# control_unit_v_1_1.net
KiCad netlist of a schematic drawn in Altium Designer
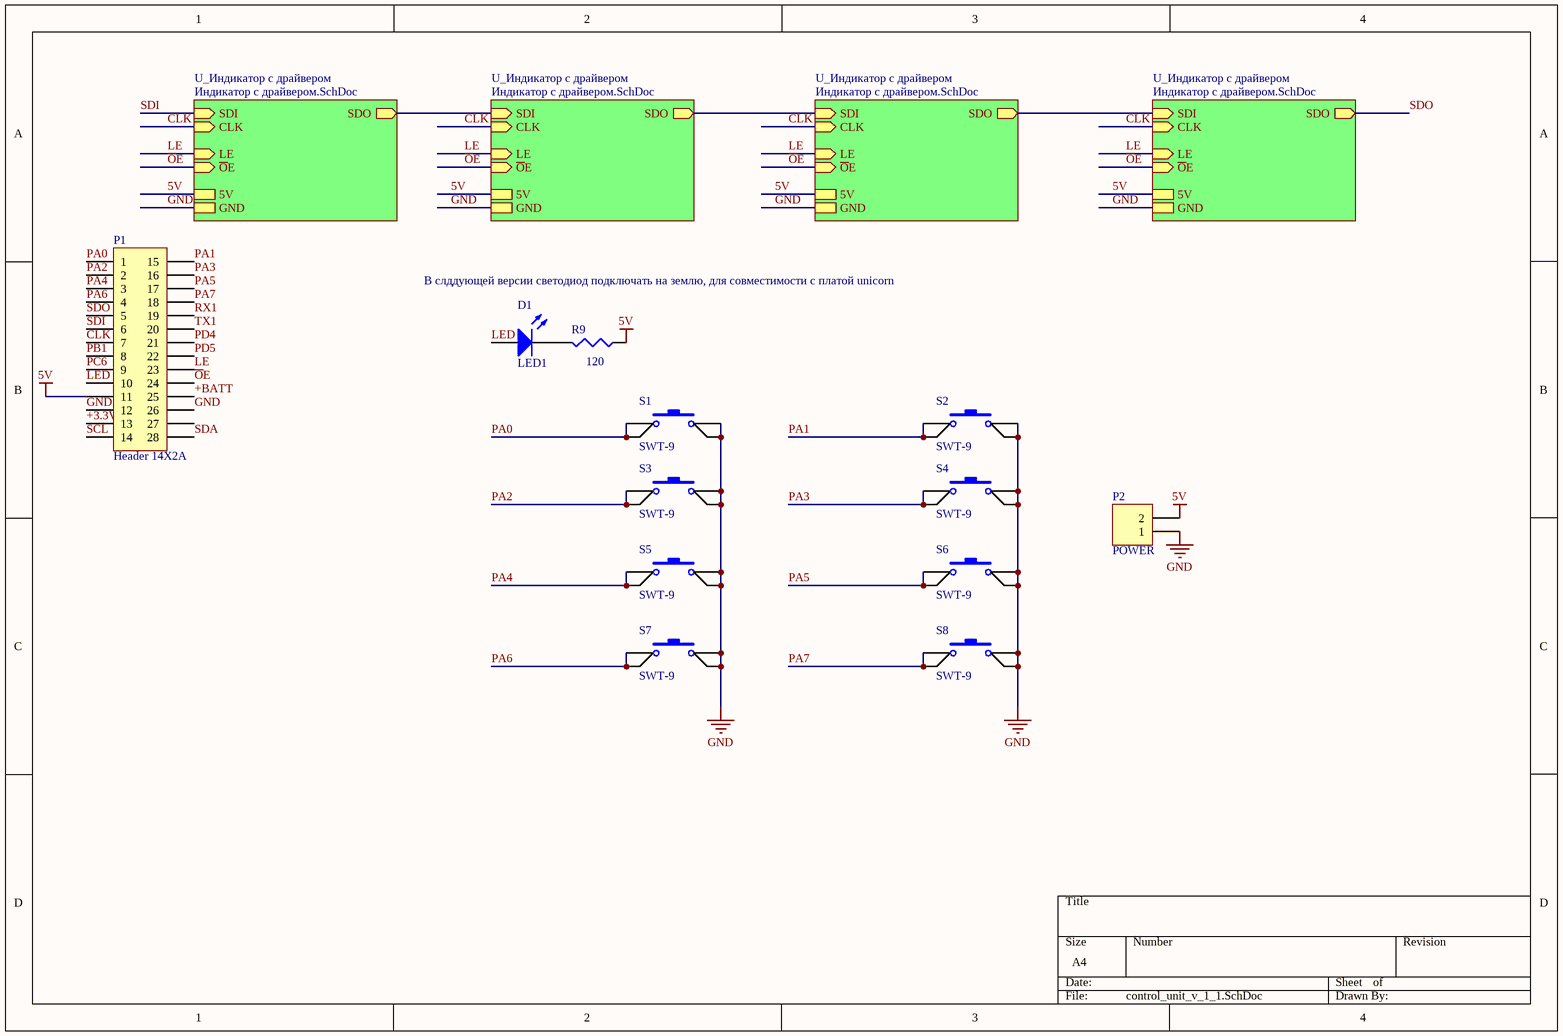
[diagram p0: control_unit_v_1_1.SchDoc]

(export (version "E")
  (design (tool "Eeschema 10.0.6"))
  (components
    (comp (ref "D1")
      (value "LED1")
      (footprint "LED-1")
      (description "Typical RED GaAs LED")
      (fields (field (name "PUBLISHER") "Altium Limited"))
      (libsource (lib "Miscellaneous Devices") (part "LED1"))
    )
    (comp (ref "P1")
      (value "Header 14X2A")
      (footprint "HDR2X14_CEN")
      (description "Header, 14-Pin, Dual row")
      (fields (field (name "PUBLISHER") "Altium Limited"))
      (libsource (lib "Miscellaneous Connectors") (part "Header 14X2A"))
    )
    (comp (ref "P2")
      (value "POWER")
      (footprint "HDR1X2H")
      (description "Header, 2-Pin, Right Angle")
      (fields (field (name "PUBLISHER") "Altium Limited"))
      (libsource (lib "Miscellaneous Connectors") (part "Header 2H"))
    )
    (comp (ref "R9")
      (value "120")
      (footprint "RESC1608L")
      (description "Resistor")
      (fields (field (name "Comment") "Res3") (field (name "PUBLISHER") "Altium Limited"))
      (libsource (lib "Miscellaneous Devices") (part "Res3"))
    )
    (comp (ref "S1")
      (value "SWT-9")
      (footprint "SWT-9")
      (description "Switch")
      (libsource (lib "LibX") (part "SWT-9"))
    )
    (comp (ref "S2")
      (value "SWT-9")
      (footprint "SWT-9")
      (description "Switch")
      (libsource (lib "LibX") (part "SWT-9"))
    )
    (comp (ref "S3")
      (value "SWT-9")
      (footprint "SWT-9")
      (description "Switch")
      (libsource (lib "LibX") (part "SWT-9"))
    )
    (comp (ref "S4")
      (value "SWT-9")
      (footprint "SWT-9")
      (description "Switch")
      (libsource (lib "LibX") (part "SWT-9"))
    )
    (comp (ref "S5")
      (value "SWT-9")
      (footprint "SWT-9")
      (description "Switch")
      (libsource (lib "LibX") (part "SWT-9"))
    )
    (comp (ref "S6")
      (value "SWT-9")
      (footprint "SWT-9")
      (description "Switch")
      (libsource (lib "LibX") (part "SWT-9"))
    )
    (comp (ref "S7")
      (value "SWT-9")
      (footprint "SWT-9")
      (description "Switch")
      (libsource (lib "LibX") (part "SWT-9"))
    )
    (comp (ref "S8")
      (value "SWT-9")
      (footprint "SWT-9")
      (description "Switch")
      (libsource (lib "LibX") (part "SWT-9"))
    )
  )
  (nets
    (net (code "1") (name "/+3.3V") (class "Default")
      (node (ref "P1") (pin "13") (pinfunction "13_13") (pintype "passive"))
    )
    (net (code "2") (name "/+BATT") (class "Default")
      (node (ref "P1") (pin "25") (pinfunction "25_25") (pintype "passive"))
    )
    (net (code "3") (name "/CLK") (class "Default")
      (node (ref "P1") (pin "7") (pinfunction "7_7") (pintype "passive"))
    )
    (net (code "4") (name "/LE") (class "Default")
      (node (ref "P1") (pin "23") (pinfunction "23_23") (pintype "passive"))
    )
    (net (code "5") (name "/LED") (class "Default")
      (node (ref "D1") (pin "1") (pinfunction "A_1") (pintype "passive"))
      (node (ref "P1") (pin "10") (pinfunction "10_10") (pintype "passive"))
    )
    (net (code "6") (name "/PA0") (class "Default")
      (node (ref "P1") (pin "1") (pinfunction "1_1") (pintype "passive"))
      (node (ref "S1") (pin "1") (pinfunction "1_1") (pintype "passive"))
      (node (ref "S1") (pin "2") (pinfunction "2_2") (pintype "passive"))
    )
    (net (code "7") (name "/PA1") (class "Default")
      (node (ref "P1") (pin "15") (pinfunction "15_15") (pintype "passive"))
      (node (ref "S2") (pin "1") (pinfunction "1_1") (pintype "passive"))
      (node (ref "S2") (pin "2") (pinfunction "2_2") (pintype "passive"))
    )
    (net (code "8") (name "/PA2") (class "Default")
      (node (ref "P1") (pin "2") (pinfunction "2_2") (pintype "passive"))
      (node (ref "S3") (pin "1") (pinfunction "1_1") (pintype "passive"))
      (node (ref "S3") (pin "2") (pinfunction "2_2") (pintype "passive"))
    )
    (net (code "9") (name "/PA3") (class "Default")
      (node (ref "P1") (pin "16") (pinfunction "16_16") (pintype "passive"))
      (node (ref "S4") (pin "1") (pinfunction "1_1") (pintype "passive"))
      (node (ref "S4") (pin "2") (pinfunction "2_2") (pintype "passive"))
    )
    (net (code "10") (name "/PA4") (class "Default")
      (node (ref "P1") (pin "3") (pinfunction "3_3") (pintype "passive"))
      (node (ref "S5") (pin "1") (pinfunction "1_1") (pintype "passive"))
      (node (ref "S5") (pin "2") (pinfunction "2_2") (pintype "passive"))
    )
    (net (code "11") (name "/PA5") (class "Default")
      (node (ref "P1") (pin "17") (pinfunction "17_17") (pintype "passive"))
      (node (ref "S6") (pin "1") (pinfunction "1_1") (pintype "passive"))
      (node (ref "S6") (pin "2") (pinfunction "2_2") (pintype "passive"))
    )
    (net (code "12") (name "/PA6") (class "Default")
      (node (ref "P1") (pin "4") (pinfunction "4_4") (pintype "passive"))
      (node (ref "S7") (pin "1") (pinfunction "1_1") (pintype "passive"))
      (node (ref "S7") (pin "2") (pinfunction "2_2") (pintype "passive"))
    )
    (net (code "13") (name "/PA7") (class "Default")
      (node (ref "P1") (pin "18") (pinfunction "18_18") (pintype "passive"))
      (node (ref "S8") (pin "1") (pinfunction "1_1") (pintype "passive"))
      (node (ref "S8") (pin "2") (pinfunction "2_2") (pintype "passive"))
    )
    (net (code "14") (name "/PB1") (class "Default")
      (node (ref "P1") (pin "8") (pinfunction "8_8") (pintype "passive"))
    )
    (net (code "15") (name "/PC6") (class "Default")
      (node (ref "P1") (pin "9") (pinfunction "9_9") (pintype "passive"))
    )
    (net (code "16") (name "/PD4") (class "Default")
      (node (ref "P1") (pin "21") (pinfunction "21_21") (pintype "passive"))
    )
    (net (code "17") (name "/PD5") (class "Default")
      (node (ref "P1") (pin "22") (pinfunction "22_22") (pintype "passive"))
    )
    (net (code "18") (name "/RX1") (class "Default")
      (node (ref "P1") (pin "19") (pinfunction "19_19") (pintype "passive"))
    )
    (net (code "19") (name "/SCL") (class "Default")
      (node (ref "P1") (pin "14") (pinfunction "14_14") (pintype "passive"))
    )
    (net (code "20") (name "/SDA") (class "Default")
      (node (ref "P1") (pin "28") (pinfunction "28_28") (pintype "passive"))
    )
    (net (code "21") (name "/SDI") (class "Default")
      (node (ref "P1") (pin "6") (pinfunction "6_6") (pintype "passive"))
    )
    (net (code "22") (name "/SDO") (class "Default")
      (node (ref "P1") (pin "5") (pinfunction "5_5") (pintype "passive"))
    )
    (net (code "26") (name "/TX1") (class "Default")
      (node (ref "P1") (pin "20") (pinfunction "20_20") (pintype "passive"))
    )
    (net (code "27") (name "/~{O}E") (class "Default")
      (node (ref "P1") (pin "24") (pinfunction "24_24") (pintype "passive"))
    )
    (net (code "28") (name "5V") (class "Default")
      (node (ref "P1") (pin "11") (pinfunction "11_11") (pintype "passive"))
      (node (ref "P2") (pin "2") (pinfunction "2_2") (pintype "passive"))
      (node (ref "R9") (pin "1") (pinfunction "1_1") (pintype "passive"))
    )
    (net (code "29") (name "GND") (class "Default")
      (node (ref "P1") (pin "12") (pinfunction "12_12") (pintype "passive"))
      (node (ref "P1") (pin "26") (pinfunction "26_26") (pintype "passive"))
      (node (ref "P2") (pin "1") (pinfunction "1_1") (pintype "passive"))
      (node (ref "S1") (pin "3") (pinfunction "3_3") (pintype "passive"))
      (node (ref "S1") (pin "4") (pinfunction "4_4") (pintype "passive"))
      (node (ref "S2") (pin "3") (pinfunction "3_3") (pintype "passive"))
      (node (ref "S2") (pin "4") (pinfunction "4_4") (pintype "passive"))
      (node (ref "S3") (pin "3") (pinfunction "3_3") (pintype "passive"))
      (node (ref "S3") (pin "4") (pinfunction "4_4") (pintype "passive"))
      (node (ref "S4") (pin "3") (pinfunction "3_3") (pintype "passive"))
      (node (ref "S4") (pin "4") (pinfunction "4_4") (pintype "passive"))
      (node (ref "S5") (pin "3") (pinfunction "3_3") (pintype "passive"))
      (node (ref "S5") (pin "4") (pinfunction "4_4") (pintype "passive"))
      (node (ref "S6") (pin "3") (pinfunction "3_3") (pintype "passive"))
      (node (ref "S6") (pin "4") (pinfunction "4_4") (pintype "passive"))
      (node (ref "S7") (pin "3") (pinfunction "3_3") (pintype "passive"))
      (node (ref "S7") (pin "4") (pinfunction "4_4") (pintype "passive"))
      (node (ref "S8") (pin "3") (pinfunction "3_3") (pintype "passive"))
      (node (ref "S8") (pin "4") (pinfunction "4_4") (pintype "passive"))
    )
    (net (code "30") (name "Net-(D1-K)") (class "Default")
      (node (ref "D1") (pin "2") (pinfunction "K_2") (pintype "passive"))
      (node (ref "R9") (pin "2") (pinfunction "2_2") (pintype "passive"))
    )
    (net (code "31") (name "unconnected-(P1-Pad27)") (class "Default")
      (node (ref "P1") (pin "27") (pinfunction "27_27") (pintype "passive"))
    )
  )
)
